# flokati-proto-r2.net
KiCad netlist of a schematic drawn in EAGLE
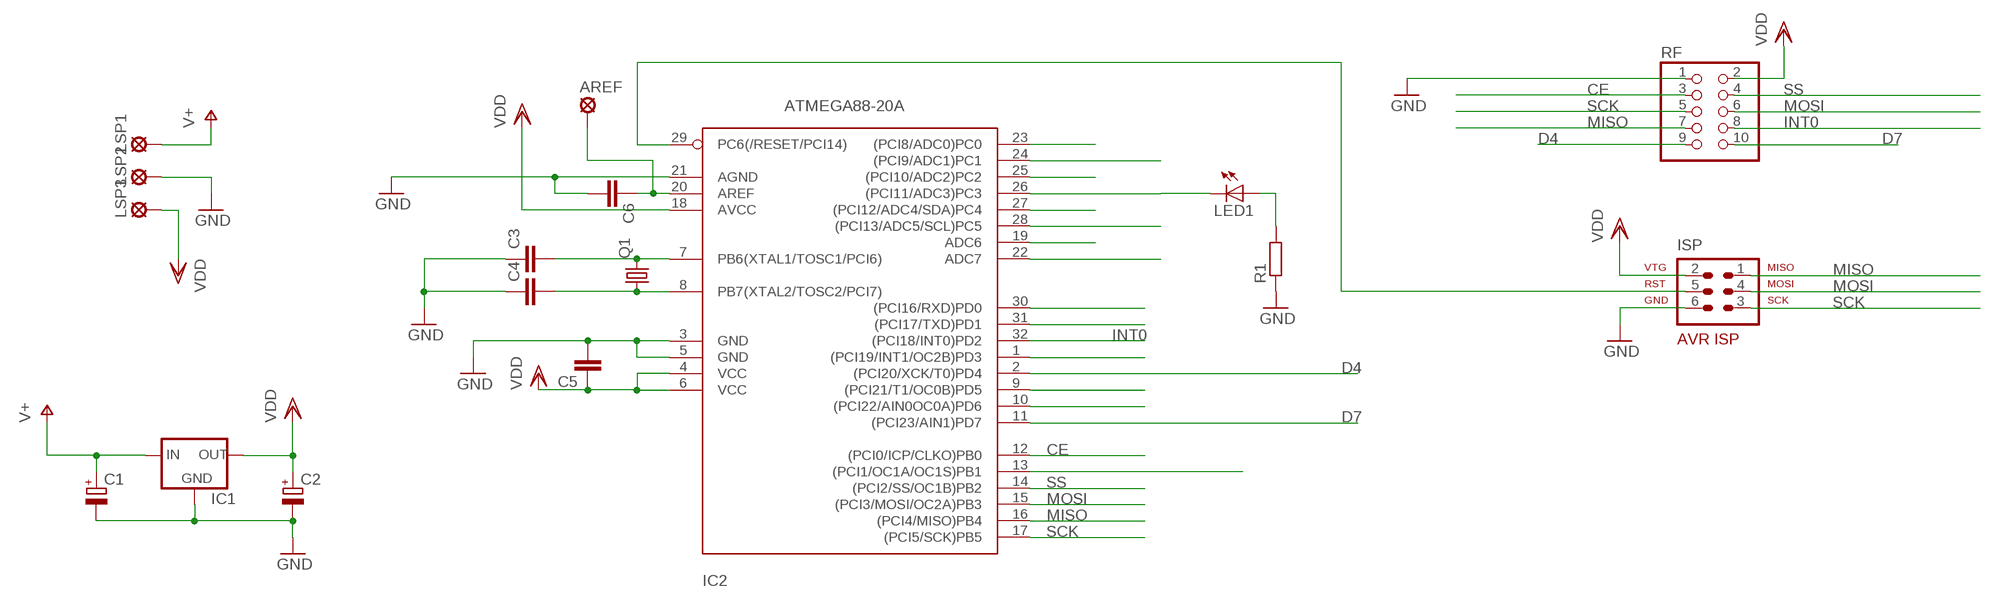
[diagram p0: schematic, sheet 1]

(export (version "E")
  (design (tool "Eeschema 10.0.6"))
  (components
    (comp (ref "AREF")
      (value "LSP10")
      (footprint "eagle-import:LSP10")
      (libsource (lib "eagle-import") (part "LSP10"))
    )
    (comp (ref "C1")
      (value "CPOL-EUE2-4")
      (footprint "eagle-import:E2-4")
      (libsource (lib "eagle-import") (part "CPOL-EUE2-4"))
    )
    (comp (ref "C2")
      (value "CPOL-EUE2-4")
      (footprint "eagle-import:E2-4")
      (libsource (lib "eagle-import") (part "CPOL-EUE2-4"))
    )
    (comp (ref "C3")
      (value "C-EUC0805K")
      (footprint "eagle-import:C0805K")
      (libsource (lib "eagle-import") (part "C-EUC0805K"))
    )
    (comp (ref "C4")
      (value "C-EUC0805K")
      (footprint "eagle-import:C0805K")
      (libsource (lib "eagle-import") (part "C-EUC0805K"))
    )
    (comp (ref "C5")
      (value "C-EUC0805K")
      (footprint "eagle-import:C0805K")
      (libsource (lib "eagle-import") (part "C-EUC0805K"))
    )
    (comp (ref "C6")
      (value "C-EUC0805K")
      (footprint "eagle-import:C0805K")
      (libsource (lib "eagle-import") (part "C-EUC0805K"))
    )
    (comp (ref "IC1")
      (value "78XXS")
      (footprint "eagle-import:78XXS")
      (libsource (lib "eagle-import") (part "78XXS"))
    )
    (comp (ref "IC2")
      (value "ATMEGA88-20A")
      (footprint "eagle-import:TQFP32-08")
      (libsource (lib "eagle-import") (part "ATMEGA88A-20"))
    )
    (comp (ref "ISP")
      (value "AVR-ISP-6")
      (footprint "eagle-import:AVR-ISP-6")
      (libsource (lib "eagle-import") (part "AVR-ISP-6"))
    )
    (comp (ref "LED1")
      (value "LEDCHIP-LED0805")
      (footprint "eagle-import:CHIP-LED0805")
      (libsource (lib "eagle-import") (part "LEDCHIP-LED0805"))
    )
    (comp (ref "LSP1")
      (value "LSP11")
      (footprint "eagle-import:LSP11")
      (libsource (lib "eagle-import") (part "LSP11"))
    )
    (comp (ref "LSP2")
      (value "LSP11")
      (footprint "eagle-import:LSP11")
      (libsource (lib "eagle-import") (part "LSP11"))
    )
    (comp (ref "LSP3")
      (value "LSP11")
      (footprint "eagle-import:LSP11")
      (libsource (lib "eagle-import") (part "LSP11"))
    )
    (comp (ref "Q1")
      (value "CRYSTALHC49U70")
      (footprint "eagle-import:HC49U70")
      (libsource (lib "eagle-import") (part "CRYSTALHC49U70"))
    )
    (comp (ref "R1")
      (value "R-EU_M0805")
      (footprint "eagle-import:M0805")
      (libsource (lib "eagle-import") (part "R-EU_M0805"))
    )
    (comp (ref "RF")
      (value "PINHD-2X5")
      (footprint "eagle-import:2X05")
      (libsource (lib "eagle-import") (part "PINHD-2X5"))
    )
  )
  (nets
    (net (code "1") (name "/CE") (class "Default")
      (node (ref "IC2") (pin "12") (pinfunction "(PCI0/ICP/CLKO)PB0_12") (pintype "bidirectional"))
      (node (ref "RF") (pin "3") (pinfunction "3_3") (pintype "passive"))
    )
    (net (code "2") (name "/D4") (class "Default")
      (node (ref "IC2") (pin "2") (pinfunction "(PCI20/XCK/T0)PD4_2") (pintype "bidirectional"))
      (node (ref "RF") (pin "9") (pinfunction "9_9") (pintype "passive"))
    )
    (net (code "3") (name "/D7") (class "Default")
      (node (ref "IC2") (pin "11") (pinfunction "(PCI23/AIN1)PD7_11") (pintype "bidirectional"))
      (node (ref "RF") (pin "10") (pinfunction "10_10") (pintype "passive"))
    )
    (net (code "4") (name "/INT0") (class "Default")
      (node (ref "IC2") (pin "32") (pinfunction "(PCI18/INT0)PD2_32") (pintype "bidirectional"))
      (node (ref "RF") (pin "8") (pinfunction "8_8") (pintype "passive"))
    )
    (net (code "5") (name "/MISO") (class "Default")
      (node (ref "IC2") (pin "16") (pinfunction "(PCI4/MISO)PB4_16") (pintype "bidirectional"))
      (node (ref "ISP") (pin "1") (pinfunction "1_1") (pintype "passive"))
      (node (ref "RF") (pin "7") (pinfunction "7_7") (pintype "passive"))
    )
    (net (code "6") (name "/MOSI") (class "Default")
      (node (ref "IC2") (pin "15") (pinfunction "(PCI3/MOSI/OC2A)PB3_15") (pintype "bidirectional"))
      (node (ref "ISP") (pin "4") (pinfunction "4_4") (pintype "passive"))
      (node (ref "RF") (pin "6") (pinfunction "6_6") (pintype "passive"))
    )
    (net (code "7") (name "/SCK") (class "Default")
      (node (ref "IC2") (pin "17") (pinfunction "(PCI5/SCK)PB5_17") (pintype "bidirectional"))
      (node (ref "ISP") (pin "3") (pinfunction "3_3") (pintype "passive"))
      (node (ref "RF") (pin "5") (pinfunction "5_5") (pintype "passive"))
    )
    (net (code "8") (name "/SS") (class "Default")
      (node (ref "IC2") (pin "14") (pinfunction "(PCI2/SS/OC1B)PB2_14") (pintype "bidirectional"))
      (node (ref "RF") (pin "4") (pinfunction "4_4") (pintype "passive"))
    )
    (net (code "9") (name "GND") (class "Default")
      (node (ref "C1") (pin "-") (pinfunction "-_-") (pintype "passive"))
      (node (ref "C2") (pin "-") (pinfunction "-_-") (pintype "passive"))
      (node (ref "C3") (pin "1") (pinfunction "1_1") (pintype "passive"))
      (node (ref "C4") (pin "1") (pinfunction "1_1") (pintype "passive"))
      (node (ref "C5") (pin "2") (pinfunction "2_2") (pintype "passive"))
      (node (ref "C6") (pin "2") (pinfunction "2_2") (pintype "passive"))
      (node (ref "IC1") (pin "GND") (pinfunction "GND_GND") (pintype "input"))
      (node (ref "IC2") (pin "21") (pinfunction "AGND_21") (pintype "bidirectional"))
      (node (ref "IC2") (pin "3") (pinfunction "GND_3") (pintype "power_in"))
      (node (ref "IC2") (pin "5") (pinfunction "GND_5") (pintype "power_in"))
      (node (ref "ISP") (pin "6") (pinfunction "6_6") (pintype "passive"))
      (node (ref "LSP2") (pin "MP") (pinfunction "MP_MP") (pintype "passive"))
      (node (ref "R1") (pin "1") (pinfunction "1_1") (pintype "passive"))
      (node (ref "RF") (pin "1") (pinfunction "1_1") (pintype "passive"))
    )
    (net (code "10") (name "Net-(IC2-(PCI11{slash}ADC3)PC3)") (class "Default")
      (node (ref "IC2") (pin "26") (pinfunction "(PCI11/ADC3)PC3_26") (pintype "bidirectional"))
      (node (ref "LED1") (pin "C") (pinfunction "C_C") (pintype "passive"))
    )
    (net (code "11") (name "Net-(IC2-AREF)") (class "Default")
      (node (ref "AREF") (pin "MP") (pinfunction "MP_MP") (pintype "passive"))
      (node (ref "C6") (pin "1") (pinfunction "1_1") (pintype "passive"))
      (node (ref "IC2") (pin "20") (pinfunction "AREF_20") (pintype "bidirectional"))
    )
    (net (code "12") (name "Net-(IC2-PB6(XTAL1{slash}TOSC1{slash}PCI6))") (class "Default")
      (node (ref "C3") (pin "2") (pinfunction "2_2") (pintype "passive"))
      (node (ref "IC2") (pin "7") (pinfunction "PB6(XTAL1/TOSC1/PCI6)_7") (pintype "bidirectional"))
      (node (ref "Q1") (pin "2") (pinfunction "2_2") (pintype "passive"))
    )
    (net (code "13") (name "Net-(IC2-PB7(XTAL2{slash}TOSC2{slash}PCI7))") (class "Default")
      (node (ref "C4") (pin "2") (pinfunction "2_2") (pintype "passive"))
      (node (ref "IC2") (pin "8") (pinfunction "PB7(XTAL2/TOSC2/PCI7)_8") (pintype "bidirectional"))
      (node (ref "Q1") (pin "1") (pinfunction "1_1") (pintype "passive"))
    )
    (net (code "14") (name "Net-(IC2-PC6({slash}RESET{slash}PCI14))") (class "Default")
      (node (ref "IC2") (pin "29") (pinfunction "PC6(/RESET/PCI14)_29") (pintype "bidirectional"))
      (node (ref "ISP") (pin "5") (pinfunction "5_5") (pintype "passive"))
    )
    (net (code "15") (name "Net-(LED1-PadA)") (class "Default")
      (node (ref "LED1") (pin "A") (pinfunction "A_A") (pintype "passive"))
      (node (ref "R1") (pin "2") (pinfunction "2_2") (pintype "passive"))
    )
    (net (code "16") (name "V+") (class "Default")
      (node (ref "C1") (pin "+") (pinfunction "+_+") (pintype "passive"))
      (node (ref "IC1") (pin "IN") (pinfunction "IN_IN") (pintype "input"))
      (node (ref "LSP1") (pin "MP") (pinfunction "MP_MP") (pintype "passive"))
    )
    (net (code "17") (name "VDD") (class "Default")
      (node (ref "C2") (pin "+") (pinfunction "+_+") (pintype "passive"))
      (node (ref "C5") (pin "1") (pinfunction "1_1") (pintype "passive"))
      (node (ref "IC1") (pin "OUT") (pinfunction "OUT_OUT") (pintype "passive"))
      (node (ref "IC2") (pin "18") (pinfunction "AVCC_18") (pintype "bidirectional"))
      (node (ref "IC2") (pin "4") (pinfunction "VCC_4") (pintype "power_in"))
      (node (ref "IC2") (pin "6") (pinfunction "VCC_6") (pintype "power_in"))
      (node (ref "ISP") (pin "2") (pinfunction "2_2") (pintype "passive"))
      (node (ref "LSP3") (pin "MP") (pinfunction "MP_MP") (pintype "passive"))
      (node (ref "RF") (pin "2") (pinfunction "2_2") (pintype "passive"))
    )
    (net (code "18") (name "unconnected-(IC2-(PCI1{slash}OC1A{slash}OC1S)PB1-Pad13)") (class "Default")
      (node (ref "IC2") (pin "13") (pinfunction "(PCI1/OC1A/OC1S)PB1_13") (pintype "bidirectional"))
    )
    (net (code "19") (name "unconnected-(IC2-(PCI8{slash}ADC0)PC0-Pad23)") (class "Default")
      (node (ref "IC2") (pin "23") (pinfunction "(PCI8/ADC0)PC0_23") (pintype "bidirectional"))
    )
    (net (code "20") (name "unconnected-(IC2-(PCI9{slash}ADC1)PC1-Pad24)") (class "Default")
      (node (ref "IC2") (pin "24") (pinfunction "(PCI9/ADC1)PC1_24") (pintype "bidirectional"))
    )
    (net (code "21") (name "unconnected-(IC2-(PCI10{slash}ADC2)PC2-Pad25)") (class "Default")
      (node (ref "IC2") (pin "25") (pinfunction "(PCI10/ADC2)PC2_25") (pintype "bidirectional"))
    )
    (net (code "22") (name "unconnected-(IC2-(PCI12{slash}ADC4{slash}SDA)PC4-Pad27)") (class "Default")
      (node (ref "IC2") (pin "27") (pinfunction "(PCI12/ADC4/SDA)PC4_27") (pintype "bidirectional"))
    )
    (net (code "23") (name "unconnected-(IC2-(PCI13{slash}ADC5{slash}SCL)PC5-Pad28)") (class "Default")
      (node (ref "IC2") (pin "28") (pinfunction "(PCI13/ADC5/SCL)PC5_28") (pintype "bidirectional"))
    )
    (net (code "24") (name "unconnected-(IC2-(PCI16{slash}RXD)PD0-Pad30)") (class "Default")
      (node (ref "IC2") (pin "30") (pinfunction "(PCI16/RXD)PD0_30") (pintype "bidirectional"))
    )
    (net (code "25") (name "unconnected-(IC2-(PCI17{slash}TXD)PD1-Pad31)") (class "Default")
      (node (ref "IC2") (pin "31") (pinfunction "(PCI17/TXD)PD1_31") (pintype "bidirectional"))
    )
    (net (code "26") (name "unconnected-(IC2-(PCI19{slash}INT1{slash}OC2B)PD3-Pad1)") (class "Default")
      (node (ref "IC2") (pin "1") (pinfunction "(PCI19/INT1/OC2B)PD3_1") (pintype "bidirectional"))
    )
    (net (code "27") (name "unconnected-(IC2-(PCI21{slash}T1{slash}OC0B)PD5-Pad9)") (class "Default")
      (node (ref "IC2") (pin "9") (pinfunction "(PCI21/T1/OC0B)PD5_9") (pintype "bidirectional"))
    )
    (net (code "28") (name "unconnected-(IC2-(PCI22{slash}AIN0OC0A)PD6-Pad10)") (class "Default")
      (node (ref "IC2") (pin "10") (pinfunction "(PCI22/AIN0OC0A)PD6_10") (pintype "bidirectional"))
    )
    (net (code "29") (name "unconnected-(IC2-ADC6-Pad19)") (class "Default")
      (node (ref "IC2") (pin "19") (pinfunction "ADC6_19") (pintype "bidirectional"))
    )
    (net (code "30") (name "unconnected-(IC2-ADC7-Pad22)") (class "Default")
      (node (ref "IC2") (pin "22") (pinfunction "ADC7_22") (pintype "bidirectional"))
    )
  )
)
